# MOD-X_V10.net
KiCad netlist of a schematic drawn in EAGLE
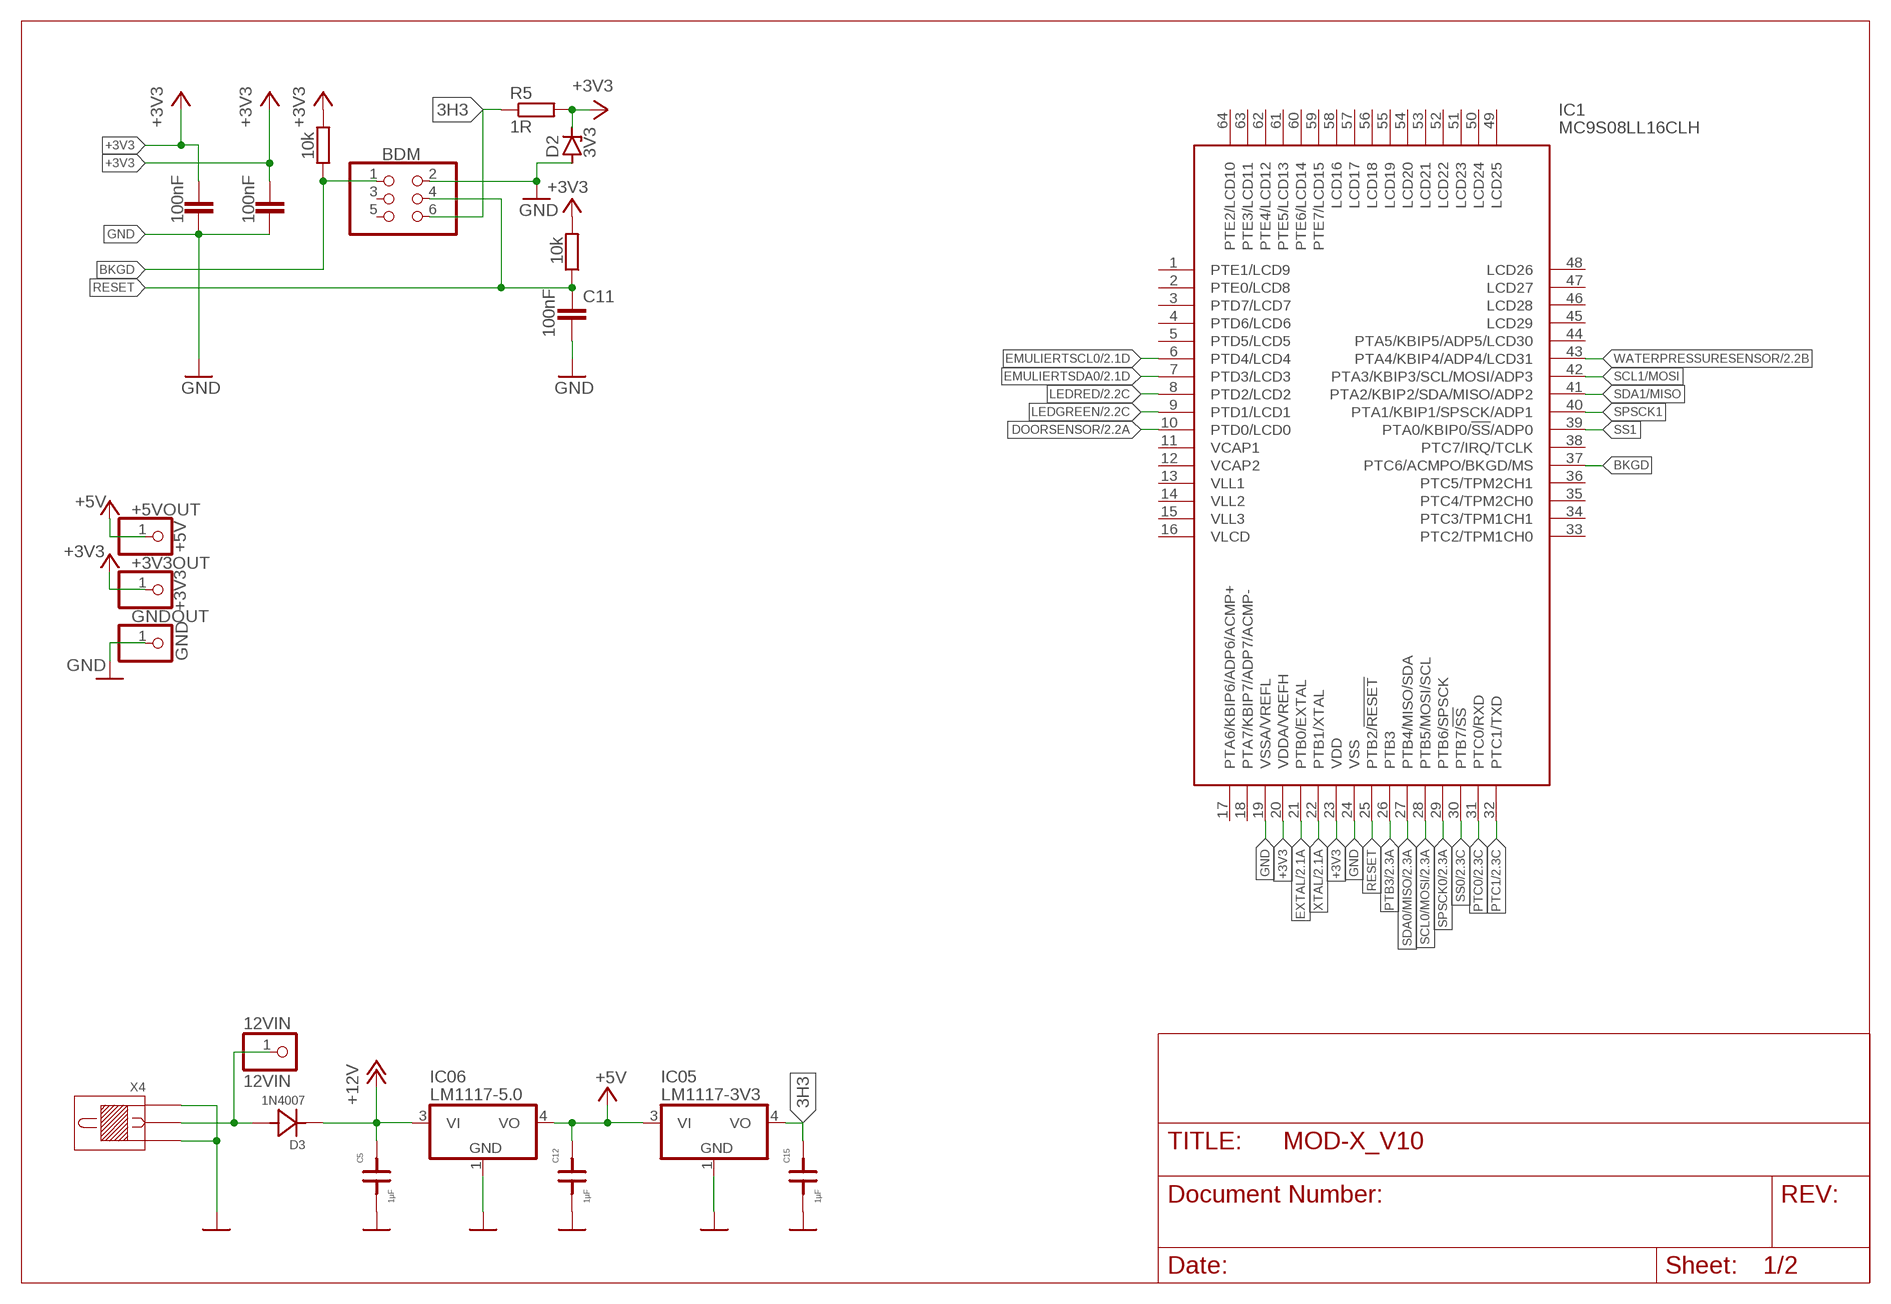
[diagram p0: schematic, sheet 1]
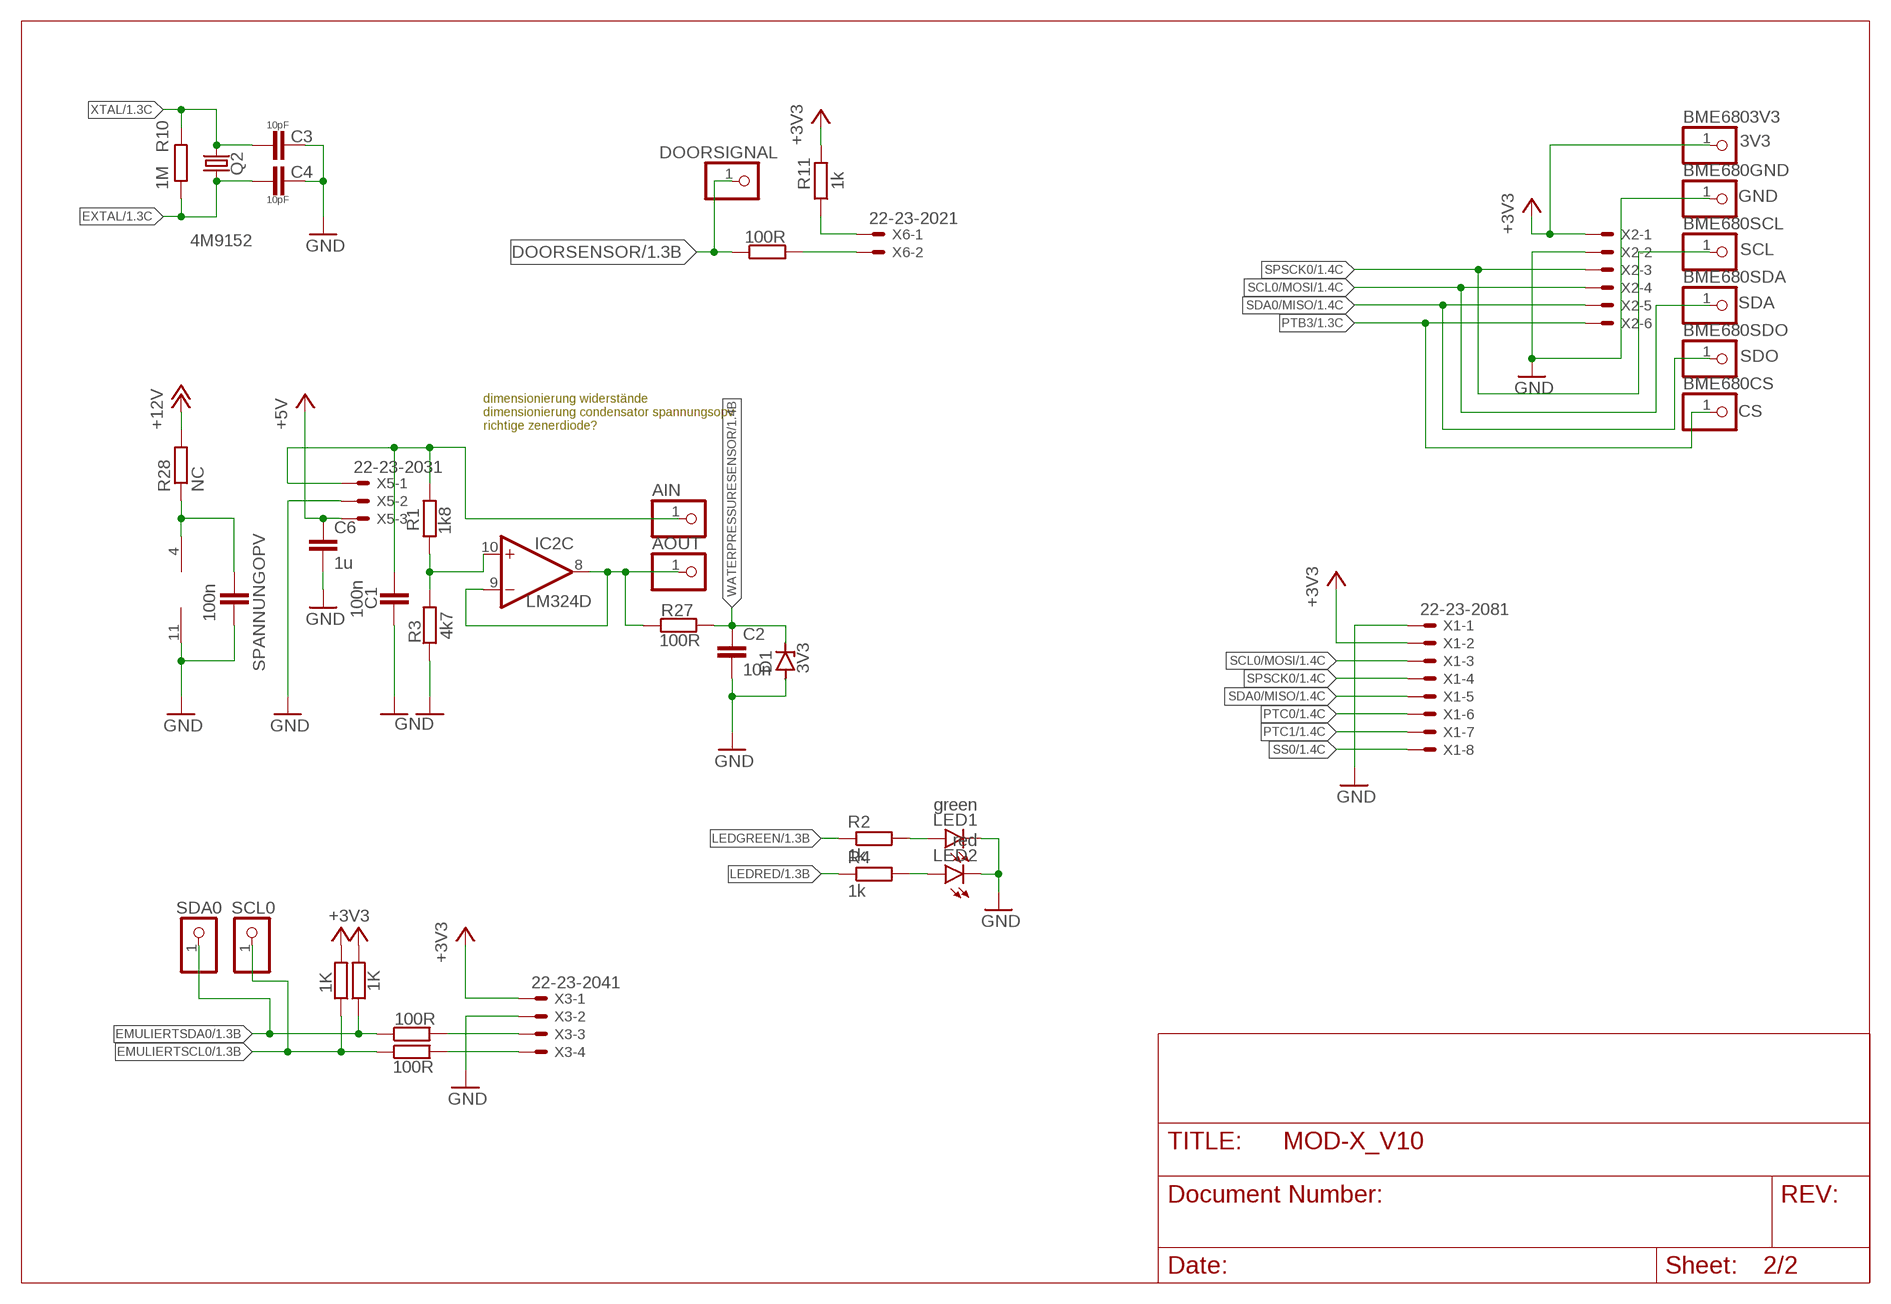
[diagram p1: schematic, sheet 2]

(export (version "E")
  (design (tool "Eeschema 10.0.6"))
  (components
    (comp (ref "AIN")
      (value "PINHD-1X1")
      (footprint "eagle-import:1X01")
      (libsource (lib "eagle-import") (part "PINHD-1X1"))
    )
    (comp (ref "AOUT")
      (value "PINHD-1X1")
      (footprint "eagle-import:1X01")
      (libsource (lib "eagle-import") (part "PINHD-1X1"))
    )
    (comp (ref "BME680CS")
      (value "CS")
      (footprint "eagle-import:1X01")
      (libsource (lib "eagle-import") (part "PINHD-1X1"))
    )
    (comp (ref "BME680GND")
      (value "GND")
      (footprint "eagle-import:1X01")
      (libsource (lib "eagle-import") (part "PINHD-1X1"))
    )
    (comp (ref "BME680SCL")
      (value "SCL")
      (footprint "eagle-import:1X01")
      (libsource (lib "eagle-import") (part "PINHD-1X1"))
    )
    (comp (ref "BME680SDA")
      (value "SDA")
      (footprint "eagle-import:1X01")
      (libsource (lib "eagle-import") (part "PINHD-1X1"))
    )
    (comp (ref "BME680SDO")
      (value "SDO")
      (footprint "eagle-import:1X01")
      (libsource (lib "eagle-import") (part "PINHD-1X1"))
    )
    (comp (ref "BME6803V3")
      (value "3V3")
      (footprint "eagle-import:1X01")
      (libsource (lib "eagle-import") (part "PINHD-1X1"))
    )
    (comp (ref "C1")
      (value "100n")
      (footprint "eagle-import:C0805")
      (libsource (lib "eagle-import") (part "C-EUC0805"))
    )
    (comp (ref "C2")
      (value "10n")
      (footprint "eagle-import:C0805")
      (libsource (lib "eagle-import") (part "C-EUC0805"))
    )
    (comp (ref "C3")
      (value "10pF")
      (footprint "eagle-import:C0805")
      (libsource (lib "eagle-import") (part "C-EUC0805"))
    )
    (comp (ref "C4")
      (value "10pF")
      (footprint "eagle-import:C0805")
      (libsource (lib "eagle-import") (part "C-EUC0805"))
    )
    (comp (ref "C6")
      (value "1u")
      (footprint "eagle-import:C0805")
      (libsource (lib "eagle-import") (part "C-EUC0805"))
    )
    (comp (ref "D1")
      (value "3V3")
      (footprint "eagle-import:SOD80C")
      (libsource (lib "eagle-import") (part "ZENER-DIODESOD80C"))
    )
    (comp (ref "DOORSIGNAL")
      (value "PINHD-1X1")
      (footprint "eagle-import:1X01")
      (libsource (lib "eagle-import") (part "PINHD-1X1"))
    )
    (comp (ref "IC2")
      (value "LM324D")
      (footprint "eagle-import:SO14")
      (libsource (lib "eagle-import") (part "LM324D"))
    )
    (comp (ref "LED1")
      (value "green")
      (footprint "eagle-import:CHIP-LED0805")
      (libsource (lib "eagle-import") (part "LEDCHIP-LED0805"))
    )
    (comp (ref "LED2")
      (value "red")
      (footprint "eagle-import:CHIP-LED0805")
      (libsource (lib "eagle-import") (part "LEDCHIP-LED0805"))
    )
    (comp (ref "Q2")
      (value "4M9152")
      (footprint "eagle-import:HC49UP")
      (libsource (lib "eagle-import") (part "CRYSTALHC49UP"))
    )
    (comp (ref "R1")
      (value "1k8")
      (footprint "eagle-import:R0805")
      (libsource (lib "eagle-import") (part "R-EU_R0805"))
    )
    (comp (ref "R2")
      (value "1k")
      (footprint "eagle-import:R0805")
      (libsource (lib "eagle-import") (part "R-EU_R0805"))
    )
    (comp (ref "R3")
      (value "4k7")
      (footprint "eagle-import:R0805")
      (libsource (lib "eagle-import") (part "R-EU_R0805"))
    )
    (comp (ref "R4")
      (value "1k")
      (footprint "eagle-import:R0805")
      (libsource (lib "eagle-import") (part "R-EU_R0805"))
    )
    (comp (ref "R6")
      (value "100R")
      (footprint "eagle-import:R0805")
      (libsource (lib "eagle-import") (part "R-EU_R0805"))
    )
    (comp (ref "R7")
      (value "100R")
      (footprint "eagle-import:R0805")
      (libsource (lib "eagle-import") (part "R-EU_R0805"))
    )
    (comp (ref "R8")
      (value "100R")
      (footprint "eagle-import:R0805")
      (libsource (lib "eagle-import") (part "R-EU_R0805"))
    )
    (comp (ref "R9")
      (value "1K")
      (footprint "eagle-import:R0805")
      (libsource (lib "eagle-import") (part "R-EU_R0805"))
    )
    (comp (ref "R10")
      (value "1M")
      (footprint "eagle-import:R0805")
      (libsource (lib "eagle-import") (part "R-EU_R0805"))
    )
    (comp (ref "R11")
      (value "1k")
      (footprint "eagle-import:R0805")
      (libsource (lib "eagle-import") (part "R-EU_R0805"))
    )
    (comp (ref "R18")
      (value "1K")
      (footprint "eagle-import:R0805")
      (libsource (lib "eagle-import") (part "R-EU_R0805"))
    )
    (comp (ref "R27")
      (value "100R")
      (footprint "eagle-import:R0805")
      (libsource (lib "eagle-import") (part "R-EU_R0805"))
    )
    (comp (ref "R28")
      (value "NC")
      (footprint "eagle-import:R0805")
      (libsource (lib "eagle-import") (part "R-EU_R0805"))
    )
    (comp (ref "SCL0")
      (value "PINHD-1X1")
      (footprint "eagle-import:1X01")
      (libsource (lib "eagle-import") (part "PINHD-1X1"))
    )
    (comp (ref "SDA0")
      (value "PINHD-1X1")
      (footprint "eagle-import:1X01")
      (libsource (lib "eagle-import") (part "PINHD-1X1"))
    )
    (comp (ref "SPANNUNGOPV")
      (value "100n")
      (footprint "eagle-import:C0805")
      (libsource (lib "eagle-import") (part "C-EUC0805"))
    )
    (comp (ref "X1")
      (value "22-23-2081")
      (footprint "eagle-import:22-23-2081")
      (fields (field (name "MF") "MOLEX"))
      (libsource (lib "eagle-import") (part "22-23-2081"))
    )
    (comp (ref "X2")
      (value "22-23-2061")
      (footprint "eagle-import:22-23-2061")
      (fields (field (name "MF") "MOLEX"))
      (libsource (lib "eagle-import") (part "22-23-2061"))
    )
    (comp (ref "X3")
      (value "22-23-2041")
      (footprint "eagle-import:22-23-2041")
      (fields (field (name "MF") "MOLEX"))
      (libsource (lib "eagle-import") (part "22-23-2041"))
    )
    (comp (ref "X5")
      (value "22-23-2031")
      (footprint "eagle-import:22-23-2031")
      (fields (field (name "MF") "MOLEX"))
      (libsource (lib "eagle-import") (part "22-23-2031"))
    )
    (comp (ref "X6")
      (value "22-23-2021")
      (footprint "eagle-import:22-23-2021")
      (fields (field (name "MF") "MOLEX"))
      (libsource (lib "eagle-import") (part "22-23-2021"))
    )
    (comp (ref "+3V3OUT")
      (value "+3V3")
      (footprint "eagle-import:1X01")
      (libsource (lib "eagle-import") (part "PINHD-1X1"))
    )
    (comp (ref "+5VOUT")
      (value "+5V")
      (footprint "eagle-import:1X01")
      (libsource (lib "eagle-import") (part "PINHD-1X1"))
    )
    (comp (ref "12VIN")
      (value "12VIN")
      (footprint "eagle-import:1X01")
      (libsource (lib "eagle-import") (part "PINHD-1X1"))
    )
    (comp (ref "BDM")
      (value "PINHD-2X3")
      (footprint "eagle-import:2X03")
      (libsource (lib "eagle-import") (part "PINHD-2X3"))
    )
    (comp (ref "C5")
      (value "1µF")
      (footprint "eagle-import:0805F")
      (libsource (lib "eagle-import") (part "C1"))
    )
    (comp (ref "C9")
      (value "100nF")
      (footprint "eagle-import:C0805")
      (libsource (lib "eagle-import") (part "C-EUC0805"))
    )
    (comp (ref "C10")
      (value "100nF")
      (footprint "eagle-import:C0805")
      (libsource (lib "eagle-import") (part "C-EUC0805"))
    )
    (comp (ref "C11")
      (value "100nF")
      (footprint "eagle-import:C0805")
      (libsource (lib "eagle-import") (part "C-EUC0805"))
    )
    (comp (ref "C12")
      (value "1µF")
      (footprint "eagle-import:0805F")
      (libsource (lib "eagle-import") (part "C1"))
    )
    (comp (ref "C15")
      (value "1µF")
      (footprint "eagle-import:0805F")
      (libsource (lib "eagle-import") (part "C1"))
    )
    (comp (ref "D2")
      (value "3V3")
      (footprint "eagle-import:SOD80C")
      (libsource (lib "eagle-import") (part "ZENER-DIODESOD80C"))
    )
    (comp (ref "D3")
      (value "1N4007")
      (footprint "eagle-import:MELF_B")
      (libsource (lib "eagle-import") (part "DHCMELF"))
    )
    (comp (ref "GNDOUT")
      (value "GND")
      (footprint "eagle-import:1X01")
      (libsource (lib "eagle-import") (part "PINHD-1X1"))
    )
    (comp (ref "IC1")
      (value "MC9S08LL16CLH")
      (footprint "eagle-import:QFP50P1200X1200X160-64N")
      (fields (field (name "MOUSER_PART_NUMBER") "841-MC9S08LL16CLH"))
      (libsource (lib "eagle-import") (part "MC9S08LL16CLH"))
    )
    (comp (ref "IC05")
      (value "LM1117-3V3")
      (footprint "eagle-import:DPAK")
      (libsource (lib "eagle-import") (part "LM1117DT"))
    )
    (comp (ref "IC06")
      (value "LM1117-5.0")
      (footprint "eagle-import:DPAK")
      (libsource (lib "eagle-import") (part "LM1117DT"))
    )
    (comp (ref "R5")
      (value "1R")
      (footprint "eagle-import:R0805")
      (libsource (lib "eagle-import") (part "R-EU_R0805"))
    )
    (comp (ref "R16")
      (value "10k")
      (footprint "eagle-import:R0805")
      (libsource (lib "eagle-import") (part "R-EU_R0805"))
    )
    (comp (ref "R17")
      (value "10k")
      (footprint "eagle-import:R0805")
      (libsource (lib "eagle-import") (part "R-EU_R0805"))
    )
    (comp (ref "X4")
      (value "SPP")
      (footprint "eagle-import:SPP")
      (libsource (lib "eagle-import") (part "SPP"))
    )
  )
  (nets
    (net (code "1") (name "+3V3") (class "Default")
      (node (ref "+3V3OUT") (pin "1") (pinfunction "1_1") (pintype "passive"))
      (node (ref "BME6803V3") (pin "1") (pinfunction "1_1") (pintype "passive"))
      (node (ref "C10") (pin "1") (pinfunction "1_1") (pintype "passive"))
      (node (ref "C9") (pin "1") (pinfunction "1_1") (pintype "passive"))
      (node (ref "D2") (pin "C") (pinfunction "C_C") (pintype "passive"))
      (node (ref "IC1") (pin "20") (pinfunction "VDDA/VREFH_20") (pintype "bidirectional"))
      (node (ref "IC1") (pin "23") (pinfunction "VDD_23") (pintype "bidirectional"))
      (node (ref "R11") (pin "2") (pinfunction "2_2") (pintype "passive"))
      (node (ref "R16") (pin "2") (pinfunction "2_2") (pintype "passive"))
      (node (ref "R17") (pin "2") (pinfunction "2_2") (pintype "passive"))
      (node (ref "R18") (pin "2") (pinfunction "2_2") (pintype "passive"))
      (node (ref "R5") (pin "2") (pinfunction "2_2") (pintype "passive"))
      (node (ref "R9") (pin "2") (pinfunction "2_2") (pintype "passive"))
      (node (ref "X1") (pin "2") (pinfunction "S_2") (pintype "passive"))
      (node (ref "X2") (pin "1") (pinfunction "S_1") (pintype "passive"))
      (node (ref "X3") (pin "1") (pinfunction "S_1") (pintype "passive"))
    )
    (net (code "2") (name "+5V") (class "Default")
      (node (ref "+5VOUT") (pin "1") (pinfunction "1_1") (pintype "passive"))
      (node (ref "C12") (pin "2") (pinfunction "2_2") (pintype "bidirectional"))
      (node (ref "C6") (pin "1") (pinfunction "1_1") (pintype "passive"))
      (node (ref "IC05") (pin "3") (pinfunction "VI_3") (pintype "input"))
      (node (ref "IC06") (pin "4") (pinfunction "VO_4") (pintype "output"))
      (node (ref "X5") (pin "3") (pinfunction "S_3") (pintype "passive"))
    )
    (net (code "3") (name "+12V") (class "Default")
      (node (ref "C5") (pin "2") (pinfunction "2_2") (pintype "bidirectional"))
      (node (ref "D3") (pin "K") (pinfunction "K_K") (pintype "bidirectional"))
      (node (ref "IC06") (pin "3") (pinfunction "VI_3") (pintype "input"))
      (node (ref "R28") (pin "2") (pinfunction "2_2") (pintype "passive"))
    )
    (net (code "4") (name "3H3") (class "Default")
      (node (ref "BDM") (pin "6") (pinfunction "6_6") (pintype "passive"))
      (node (ref "C15") (pin "2") (pinfunction "2_2") (pintype "bidirectional"))
      (node (ref "IC05") (pin "4") (pinfunction "VO_4") (pintype "output"))
      (node (ref "R5") (pin "1") (pinfunction "1_1") (pintype "passive"))
    )
    (net (code "5") (name "BKGD") (class "Default")
      (node (ref "BDM") (pin "1") (pinfunction "1_1") (pintype "passive"))
      (node (ref "IC1") (pin "37") (pinfunction "PTC6/ACMPO/BKGD/MS_37") (pintype "bidirectional"))
      (node (ref "R16") (pin "1") (pinfunction "1_1") (pintype "passive"))
    )
    (net (code "6") (name "DOORSENSOR") (class "Default")
      (node (ref "DOORSIGNAL") (pin "1") (pinfunction "1_1") (pintype "passive"))
      (node (ref "IC1") (pin "10") (pinfunction "PTD0/LCD0_10") (pintype "bidirectional"))
      (node (ref "R6") (pin "1") (pinfunction "1_1") (pintype "passive"))
    )
    (net (code "7") (name "EMULIERTSCL0") (class "Default")
      (node (ref "IC1") (pin "6") (pinfunction "PTD4/LCD4_6") (pintype "bidirectional"))
      (node (ref "R18") (pin "1") (pinfunction "1_1") (pintype "passive"))
      (node (ref "R8") (pin "1") (pinfunction "1_1") (pintype "passive"))
      (node (ref "SCL0") (pin "1") (pinfunction "1_1") (pintype "passive"))
    )
    (net (code "8") (name "EMULIERTSDA0") (class "Default")
      (node (ref "IC1") (pin "7") (pinfunction "PTD3/LCD3_7") (pintype "bidirectional"))
      (node (ref "R7") (pin "1") (pinfunction "1_1") (pintype "passive"))
      (node (ref "R9") (pin "1") (pinfunction "1_1") (pintype "passive"))
      (node (ref "SDA0") (pin "1") (pinfunction "1_1") (pintype "passive"))
    )
    (net (code "9") (name "EXTAL") (class "Default")
      (node (ref "C4") (pin "1") (pinfunction "1_1") (pintype "passive"))
      (node (ref "IC1") (pin "21") (pinfunction "PTB0/EXTAL_21") (pintype "bidirectional"))
      (node (ref "Q2") (pin "1") (pinfunction "1_1") (pintype "passive"))
      (node (ref "R10") (pin "1") (pinfunction "1_1") (pintype "passive"))
    )
    (net (code "10") (name "GND") (class "Default")
      (node (ref "BDM") (pin "2") (pinfunction "2_2") (pintype "passive"))
      (node (ref "BME680GND") (pin "1") (pinfunction "1_1") (pintype "passive"))
      (node (ref "C1") (pin "2") (pinfunction "2_2") (pintype "passive"))
      (node (ref "C10") (pin "2") (pinfunction "2_2") (pintype "passive"))
      (node (ref "C11") (pin "2") (pinfunction "2_2") (pintype "passive"))
      (node (ref "C12") (pin "1") (pinfunction "1_1") (pintype "bidirectional"))
      (node (ref "C15") (pin "1") (pinfunction "1_1") (pintype "bidirectional"))
      (node (ref "C2") (pin "2") (pinfunction "2_2") (pintype "passive"))
      (node (ref "C3") (pin "2") (pinfunction "2_2") (pintype "passive"))
      (node (ref "C4") (pin "2") (pinfunction "2_2") (pintype "passive"))
      (node (ref "C5") (pin "1") (pinfunction "1_1") (pintype "bidirectional"))
      (node (ref "C6") (pin "2") (pinfunction "2_2") (pintype "passive"))
      (node (ref "C9") (pin "2") (pinfunction "2_2") (pintype "passive"))
      (node (ref "D1") (pin "A") (pinfunction "A_A") (pintype "passive"))
      (node (ref "D2") (pin "A") (pinfunction "A_A") (pintype "passive"))
      (node (ref "GNDOUT") (pin "1") (pinfunction "1_1") (pintype "passive"))
      (node (ref "IC05") (pin "1") (pinfunction "GND_1") (pintype "input"))
      (node (ref "IC06") (pin "1") (pinfunction "GND_1") (pintype "input"))
      (node (ref "IC1") (pin "19") (pinfunction "VSSA/VREFL_19") (pintype "bidirectional"))
      (node (ref "IC1") (pin "24") (pinfunction "VSS_24") (pintype "bidirectional"))
      (node (ref "IC2") (pin "11") (pinfunction "V-_11") (pintype "power_in"))
      (node (ref "LED1") (pin "C") (pinfunction "C_C") (pintype "passive"))
      (node (ref "LED2") (pin "C") (pinfunction "C_C") (pintype "passive"))
      (node (ref "R3") (pin "1") (pinfunction "1_1") (pintype "passive"))
      (node (ref "SPANNUNGOPV") (pin "2") (pinfunction "2_2") (pintype "passive"))
      (node (ref "X1") (pin "1") (pinfunction "S_1") (pintype "passive"))
      (node (ref "X2") (pin "2") (pinfunction "S_2") (pintype "passive"))
      (node (ref "X3") (pin "2") (pinfunction "S_2") (pintype "passive"))
      (node (ref "X4") (pin "1") (pinfunction "1_1") (pintype "bidirectional"))
      (node (ref "X4") (pin "3") (pinfunction "3_3") (pintype "bidirectional"))
      (node (ref "X5") (pin "2") (pinfunction "S_2") (pintype "passive"))
    )
    (net (code "11") (name "LEDGREEN") (class "Default")
      (node (ref "IC1") (pin "9") (pinfunction "PTD1/LCD1_9") (pintype "bidirectional"))
      (node (ref "R2") (pin "1") (pinfunction "1_1") (pintype "passive"))
    )
    (net (code "12") (name "LEDRED") (class "Default")
      (node (ref "IC1") (pin "8") (pinfunction "PTD2/LCD2_8") (pintype "bidirectional"))
      (node (ref "R4") (pin "1") (pinfunction "1_1") (pintype "passive"))
    )
    (net (code "13") (name "Net-(12VIN-Pad1)") (class "Default")
      (node (ref "12VIN") (pin "1") (pinfunction "1_1") (pintype "passive"))
      (node (ref "D3") (pin "A") (pinfunction "A_A") (pintype "bidirectional"))
      (node (ref "X4") (pin "2") (pinfunction "2_2") (pintype "bidirectional"))
    )
    (net (code "14") (name "Net-(IC2C-+IN)") (class "Default")
      (node (ref "IC2") (pin "10") (pinfunction "+IN_10") (pintype "input"))
      (node (ref "R1") (pin "1") (pinfunction "1_1") (pintype "passive"))
      (node (ref "R3") (pin "2") (pinfunction "2_2") (pintype "passive"))
    )
    (net (code "15") (name "Net-(IC2C--IN)") (class "Default")
      (node (ref "AOUT") (pin "1") (pinfunction "1_1") (pintype "passive"))
      (node (ref "IC2") (pin "8") (pinfunction "OUT_8") (pintype "output"))
      (node (ref "IC2") (pin "9") (pinfunction "-IN_9") (pintype "input"))
      (node (ref "R27") (pin "1") (pinfunction "1_1") (pintype "passive"))
    )
    (net (code "16") (name "Net-(IC2E-V+)") (class "Default")
      (node (ref "IC2") (pin "4") (pinfunction "V+_4") (pintype "power_in"))
      (node (ref "R28") (pin "1") (pinfunction "1_1") (pintype "passive"))
      (node (ref "SPANNUNGOPV") (pin "1") (pinfunction "1_1") (pintype "passive"))
    )
    (net (code "17") (name "Net-(LED1-PadA)") (class "Default")
      (node (ref "LED1") (pin "A") (pinfunction "A_A") (pintype "passive"))
      (node (ref "R2") (pin "2") (pinfunction "2_2") (pintype "passive"))
    )
    (net (code "18") (name "Net-(LED2-PadA)") (class "Default")
      (node (ref "LED2") (pin "A") (pinfunction "A_A") (pintype "passive"))
      (node (ref "R4") (pin "2") (pinfunction "2_2") (pintype "passive"))
    )
    (net (code "19") (name "Net-(X3C-S)") (class "Default")
      (node (ref "R7") (pin "2") (pinfunction "2_2") (pintype "passive"))
      (node (ref "X3") (pin "3") (pinfunction "S_3") (pintype "passive"))
    )
    (net (code "20") (name "Net-(X3D-S)") (class "Default")
      (node (ref "R8") (pin "2") (pinfunction "2_2") (pintype "passive"))
      (node (ref "X3") (pin "4") (pinfunction "S_4") (pintype "passive"))
    )
    (net (code "21") (name "Net-(X5A-S)") (class "Default")
      (node (ref "AIN") (pin "1") (pinfunction "1_1") (pintype "passive"))
      (node (ref "C1") (pin "1") (pinfunction "1_1") (pintype "passive"))
      (node (ref "R1") (pin "2") (pinfunction "2_2") (pintype "passive"))
      (node (ref "X5") (pin "1") (pinfunction "S_1") (pintype "passive"))
    )
    (net (code "22") (name "Net-(X6A-S)") (class "Default")
      (node (ref "R11") (pin "1") (pinfunction "1_1") (pintype "passive"))
      (node (ref "X6") (pin "1") (pinfunction "S_1") (pintype "passive"))
    )
    (net (code "23") (name "Net-(X6B-S)") (class "Default")
      (node (ref "R6") (pin "2") (pinfunction "2_2") (pintype "passive"))
      (node (ref "X6") (pin "2") (pinfunction "S_2") (pintype "passive"))
    )
    (net (code "24") (name "PTB3") (class "Default")
      (node (ref "BME680CS") (pin "1") (pinfunction "1_1") (pintype "passive"))
      (node (ref "IC1") (pin "26") (pinfunction "PTB3_26") (pintype "bidirectional"))
      (node (ref "X2") (pin "6") (pinfunction "S_6") (pintype "passive"))
    )
    (net (code "25") (name "PTC0") (class "Default")
      (node (ref "IC1") (pin "31") (pinfunction "PTC0/RXD_31") (pintype "bidirectional"))
      (node (ref "X1") (pin "6") (pinfunction "S_6") (pintype "passive"))
    )
    (net (code "26") (name "PTC1") (class "Default")
      (node (ref "IC1") (pin "32") (pinfunction "PTC1/TXD_32") (pintype "bidirectional"))
      (node (ref "X1") (pin "7") (pinfunction "S_7") (pintype "passive"))
    )
    (net (code "27") (name "RESET") (class "Default")
      (node (ref "BDM") (pin "4") (pinfunction "4_4") (pintype "passive"))
      (node (ref "C11") (pin "1") (pinfunction "1_1") (pintype "passive"))
      (node (ref "IC1") (pin "25") (pinfunction "PTB2/~{RESET}_25") (pintype "bidirectional"))
      (node (ref "R17") (pin "1") (pinfunction "1_1") (pintype "passive"))
    )
    (net (code "28") (name "SCL0{slash}MOSI") (class "Default")
      (node (ref "BME680SDA") (pin "1") (pinfunction "1_1") (pintype "passive"))
      (node (ref "IC1") (pin "28") (pinfunction "PTB5/MOSI/SCL_28") (pintype "bidirectional"))
      (node (ref "X1") (pin "3") (pinfunction "S_3") (pintype "passive"))
      (node (ref "X2") (pin "4") (pinfunction "S_4") (pintype "passive"))
    )
    (net (code "29") (name "SCL1{slash}MOSI") (class "Default")
      (node (ref "IC1") (pin "42") (pinfunction "PTA3/KBIP3/SCL/MOSI/ADP3_42") (pintype "bidirectional"))
    )
    (net (code "30") (name "SDA0{slash}MISO") (class "Default")
      (node (ref "BME680SDO") (pin "1") (pinfunction "1_1") (pintype "passive"))
      (node (ref "IC1") (pin "27") (pinfunction "PTB4/MISO/SDA_27") (pintype "bidirectional"))
      (node (ref "X1") (pin "5") (pinfunction "S_5") (pintype "passive"))
      (node (ref "X2") (pin "5") (pinfunction "S_5") (pintype "passive"))
    )
    (net (code "31") (name "SDA1{slash}MISO") (class "Default")
      (node (ref "IC1") (pin "41") (pinfunction "PTA2/KBIP2/SDA/MISO/ADP2_41") (pintype "bidirectional"))
    )
    (net (code "32") (name "SPSCK0") (class "Default")
      (node (ref "BME680SCL") (pin "1") (pinfunction "1_1") (pintype "passive"))
      (node (ref "IC1") (pin "29") (pinfunction "PTB6/SPSCK_29") (pintype "bidirectional"))
      (node (ref "X1") (pin "4") (pinfunction "S_4") (pintype "passive"))
      (node (ref "X2") (pin "3") (pinfunction "S_3") (pintype "passive"))
    )
    (net (code "33") (name "SPSCK1") (class "Default")
      (node (ref "IC1") (pin "40") (pinfunction "PTA1/KBIP1/SPSCK/ADP1_40") (pintype "bidirectional"))
    )
    (net (code "34") (name "SS0") (class "Default")
      (node (ref "IC1") (pin "30") (pinfunction "PTB7/~{SS}_30") (pintype "bidirectional"))
      (node (ref "X1") (pin "8") (pinfunction "S_8") (pintype "passive"))
    )
    (net (code "35") (name "SS1") (class "Default")
      (node (ref "IC1") (pin "39") (pinfunction "PTA0/KBIP0/~{SS}/ADP0_39") (pintype "bidirectional"))
    )
    (net (code "36") (name "WATERPRESSURESENSOR") (class "Default")
      (node (ref "C2") (pin "1") (pinfunction "1_1") (pintype "passive"))
      (node (ref "D1") (pin "C") (pinfunction "C_C") (pintype "passive"))
      (node (ref "IC1") (pin "43") (pinfunction "PTA4/KBIP4/ADP4/LCD31_43") (pintype "bidirectional"))
      (node (ref "R27") (pin "2") (pinfunction "2_2") (pintype "passive"))
    )
    (net (code "37") (name "XTAL") (class "Default")
      (node (ref "C3") (pin "1") (pinfunction "1_1") (pintype "passive"))
      (node (ref "IC1") (pin "22") (pinfunction "PTB1/XTAL_22") (pintype "bidirectional"))
      (node (ref "Q2") (pin "2") (pinfunction "2_2") (pintype "passive"))
      (node (ref "R10") (pin "2") (pinfunction "2_2") (pintype "passive"))
    )
    (net (code "38") (name "unconnected-(BDM-Pad3)") (class "Default")
      (node (ref "BDM") (pin "3") (pinfunction "3_3") (pintype "passive"))
    )
    (net (code "39") (name "unconnected-(BDM-Pad5)") (class "Default")
      (node (ref "BDM") (pin "5") (pinfunction "5_5") (pintype "passive"))
    )
    (net (code "40") (name "unconnected-(IC1-LCD16-Pad58)") (class "Default")
      (node (ref "IC1") (pin "58") (pinfunction "LCD16_58") (pintype "bidirectional"))
    )
    (net (code "41") (name "unconnected-(IC1-LCD17-Pad57)") (class "Default")
      (node (ref "IC1") (pin "57") (pinfunction "LCD17_57") (pintype "bidirectional"))
    )
    (net (code "42") (name "unconnected-(IC1-LCD18-Pad56)") (class "Default")
      (node (ref "IC1") (pin "56") (pinfunction "LCD18_56") (pintype "bidirectional"))
    )
    (net (code "43") (name "unconnected-(IC1-LCD19-Pad55)") (class "Default")
      (node (ref "IC1") (pin "55") (pinfunction "LCD19_55") (pintype "bidirectional"))
    )
    (net (code "44") (name "unconnected-(IC1-LCD20-Pad54)") (class "Default")
      (node (ref "IC1") (pin "54") (pinfunction "LCD20_54") (pintype "bidirectional"))
    )
    (net (code "45") (name "unconnected-(IC1-LCD21-Pad53)") (class "Default")
      (node (ref "IC1") (pin "53") (pinfunction "LCD21_53") (pintype "bidirectional"))
    )
    (net (code "46") (name "unconnected-(IC1-LCD22-Pad52)") (class "Default")
      (node (ref "IC1") (pin "52") (pinfunction "LCD22_52") (pintype "bidirectional"))
    )
    (net (code "47") (name "unconnected-(IC1-LCD23-Pad51)") (class "Default")
      (node (ref "IC1") (pin "51") (pinfunction "LCD23_51") (pintype "bidirectional"))
    )
    (net (code "48") (name "unconnected-(IC1-LCD24-Pad50)") (class "Default")
      (node (ref "IC1") (pin "50") (pinfunction "LCD24_50") (pintype "bidirectional"))
    )
    (net (code "49") (name "unconnected-(IC1-LCD25-Pad49)") (class "Default")
      (node (ref "IC1") (pin "49") (pinfunction "LCD25_49") (pintype "bidirectional"))
    )
    (net (code "50") (name "unconnected-(IC1-LCD26-Pad48)") (class "Default")
      (node (ref "IC1") (pin "48") (pinfunction "LCD26_48") (pintype "bidirectional"))
    )
    (net (code "51") (name "unconnected-(IC1-LCD27-Pad47)") (class "Default")
      (node (ref "IC1") (pin "47") (pinfunction "LCD27_47") (pintype "bidirectional"))
    )
    (net (code "52") (name "unconnected-(IC1-LCD28-Pad46)") (class "Default")
      (node (ref "IC1") (pin "46") (pinfunction "LCD28_46") (pintype "bidirectional"))
    )
    (net (code "53") (name "unconnected-(IC1-LCD29-Pad45)") (class "Default")
      (node (ref "IC1") (pin "45") (pinfunction "LCD29_45") (pintype "bidirectional"))
    )
    (net (code "54") (name "unconnected-(IC1-PTA5{slash}KBIP5{slash}ADP5{slash}LCD30-Pad44)") (class "Default")
      (node (ref "IC1") (pin "44") (pinfunction "PTA5/KBIP5/ADP5/LCD30_44") (pintype "bidirectional"))
    )
    (net (code "55") (name "unconnected-(IC1-PTA6{slash}KBIP6{slash}ADP6{slash}ACMP+-Pad17)") (class "Default")
      (node (ref "IC1") (pin "17") (pinfunction "PTA6/KBIP6/ADP6/ACMP+_17") (pintype "bidirectional"))
    )
    (net (code "56") (name "unconnected-(IC1-PTA7{slash}KBIP7{slash}ADP7{slash}ACMP--Pad18)") (class "Default")
      (node (ref "IC1") (pin "18") (pinfunction "PTA7/KBIP7/ADP7/ACMP-_18") (pintype "bidirectional"))
    )
    (net (code "57") (name "unconnected-(IC1-PTC2{slash}TPM1CH0-Pad33)") (class "Default")
      (node (ref "IC1") (pin "33") (pinfunction "PTC2/TPM1CH0_33") (pintype "bidirectional"))
    )
    (net (code "58") (name "unconnected-(IC1-PTC3{slash}TPM1CH1-Pad34)") (class "Default")
      (node (ref "IC1") (pin "34") (pinfunction "PTC3/TPM1CH1_34") (pintype "bidirectional"))
    )
    (net (code "59") (name "unconnected-(IC1-PTC4{slash}TPM2CH0-Pad35)") (class "Default")
      (node (ref "IC1") (pin "35") (pinfunction "PTC4/TPM2CH0_35") (pintype "bidirectional"))
    )
    (net (code "60") (name "unconnected-(IC1-PTC5{slash}TPM2CH1-Pad36)") (class "Default")
      (node (ref "IC1") (pin "36") (pinfunction "PTC5/TPM2CH1_36") (pintype "bidirectional"))
    )
    (net (code "61") (name "unconnected-(IC1-PTC7{slash}IRQ{slash}TCLK-Pad38)") (class "Default")
      (node (ref "IC1") (pin "38") (pinfunction "PTC7/IRQ/TCLK_38") (pintype "bidirectional"))
    )
    (net (code "62") (name "unconnected-(IC1-PTD5{slash}LCD5-Pad5)") (class "Default")
      (node (ref "IC1") (pin "5") (pinfunction "PTD5/LCD5_5") (pintype "bidirectional"))
    )
    (net (code "63") (name "unconnected-(IC1-PTD6{slash}LCD6-Pad4)") (class "Default")
      (node (ref "IC1") (pin "4") (pinfunction "PTD6/LCD6_4") (pintype "bidirectional"))
    )
    (net (code "64") (name "unconnected-(IC1-PTD7{slash}LCD7-Pad3)") (class "Default")
      (node (ref "IC1") (pin "3") (pinfunction "PTD7/LCD7_3") (pintype "bidirectional"))
    )
    (net (code "65") (name "unconnected-(IC1-PTE0{slash}LCD8-Pad2)") (class "Default")
      (node (ref "IC1") (pin "2") (pinfunction "PTE0/LCD8_2") (pintype "bidirectional"))
    )
    (net (code "66") (name "unconnected-(IC1-PTE1{slash}LCD9-Pad1)") (class "Default")
      (node (ref "IC1") (pin "1") (pinfunction "PTE1/LCD9_1") (pintype "bidirectional"))
    )
    (net (code "67") (name "unconnected-(IC1-PTE2{slash}LCD10-Pad64)") (class "Default")
      (node (ref "IC1") (pin "64") (pinfunction "PTE2/LCD10_64") (pintype "bidirectional"))
    )
    (net (code "68") (name "unconnected-(IC1-PTE3{slash}LCD11-Pad63)") (class "Default")
      (node (ref "IC1") (pin "63") (pinfunction "PTE3/LCD11_63") (pintype "bidirectional"))
    )
    (net (code "69") (name "unconnected-(IC1-PTE4{slash}LCD12-Pad62)") (class "Default")
      (node (ref "IC1") (pin "62") (pinfunction "PTE4/LCD12_62") (pintype "bidirectional"))
    )
    (net (code "70") (name "unconnected-(IC1-PTE5{slash}LCD13-Pad61)") (class "Default")
      (node (ref "IC1") (pin "61") (pinfunction "PTE5/LCD13_61") (pintype "bidirectional"))
    )
    (net (code "71") (name "unconnected-(IC1-PTE6{slash}LCD14-Pad60)") (class "Default")
      (node (ref "IC1") (pin "60") (pinfunction "PTE6/LCD14_60") (pintype "bidirectional"))
    )
    (net (code "72") (name "unconnected-(IC1-PTE7{slash}LCD15-Pad59)") (class "Default")
      (node (ref "IC1") (pin "59") (pinfunction "PTE7/LCD15_59") (pintype "bidirectional"))
    )
    (net (code "73") (name "unconnected-(IC1-VCAP1-Pad11)") (class "Default")
      (node (ref "IC1") (pin "11") (pinfunction "VCAP1_11") (pintype "bidirectional"))
    )
    (net (code "74") (name "unconnected-(IC1-VCAP2-Pad12)") (class "Default")
      (node (ref "IC1") (pin "12") (pinfunction "VCAP2_12") (pintype "bidirectional"))
    )
    (net (code "75") (name "unconnected-(IC1-VLCD-Pad16)") (class "Default")
      (node (ref "IC1") (pin "16") (pinfunction "VLCD_16") (pintype "bidirectional"))
    )
    (net (code "76") (name "unconnected-(IC1-VLL1-Pad13)") (class "Default")
      (node (ref "IC1") (pin "13") (pinfunction "VLL1_13") (pintype "bidirectional"))
    )
    (net (code "77") (name "unconnected-(IC1-VLL2-Pad14)") (class "Default")
      (node (ref "IC1") (pin "14") (pinfunction "VLL2_14") (pintype "bidirectional"))
    )
    (net (code "78") (name "unconnected-(IC1-VLL3-Pad15)") (class "Default")
      (node (ref "IC1") (pin "15") (pinfunction "VLL3_15") (pintype "bidirectional"))
    )
  )
)
